# vreg.net
KiCad netlist of a schematic drawn in EAGLE
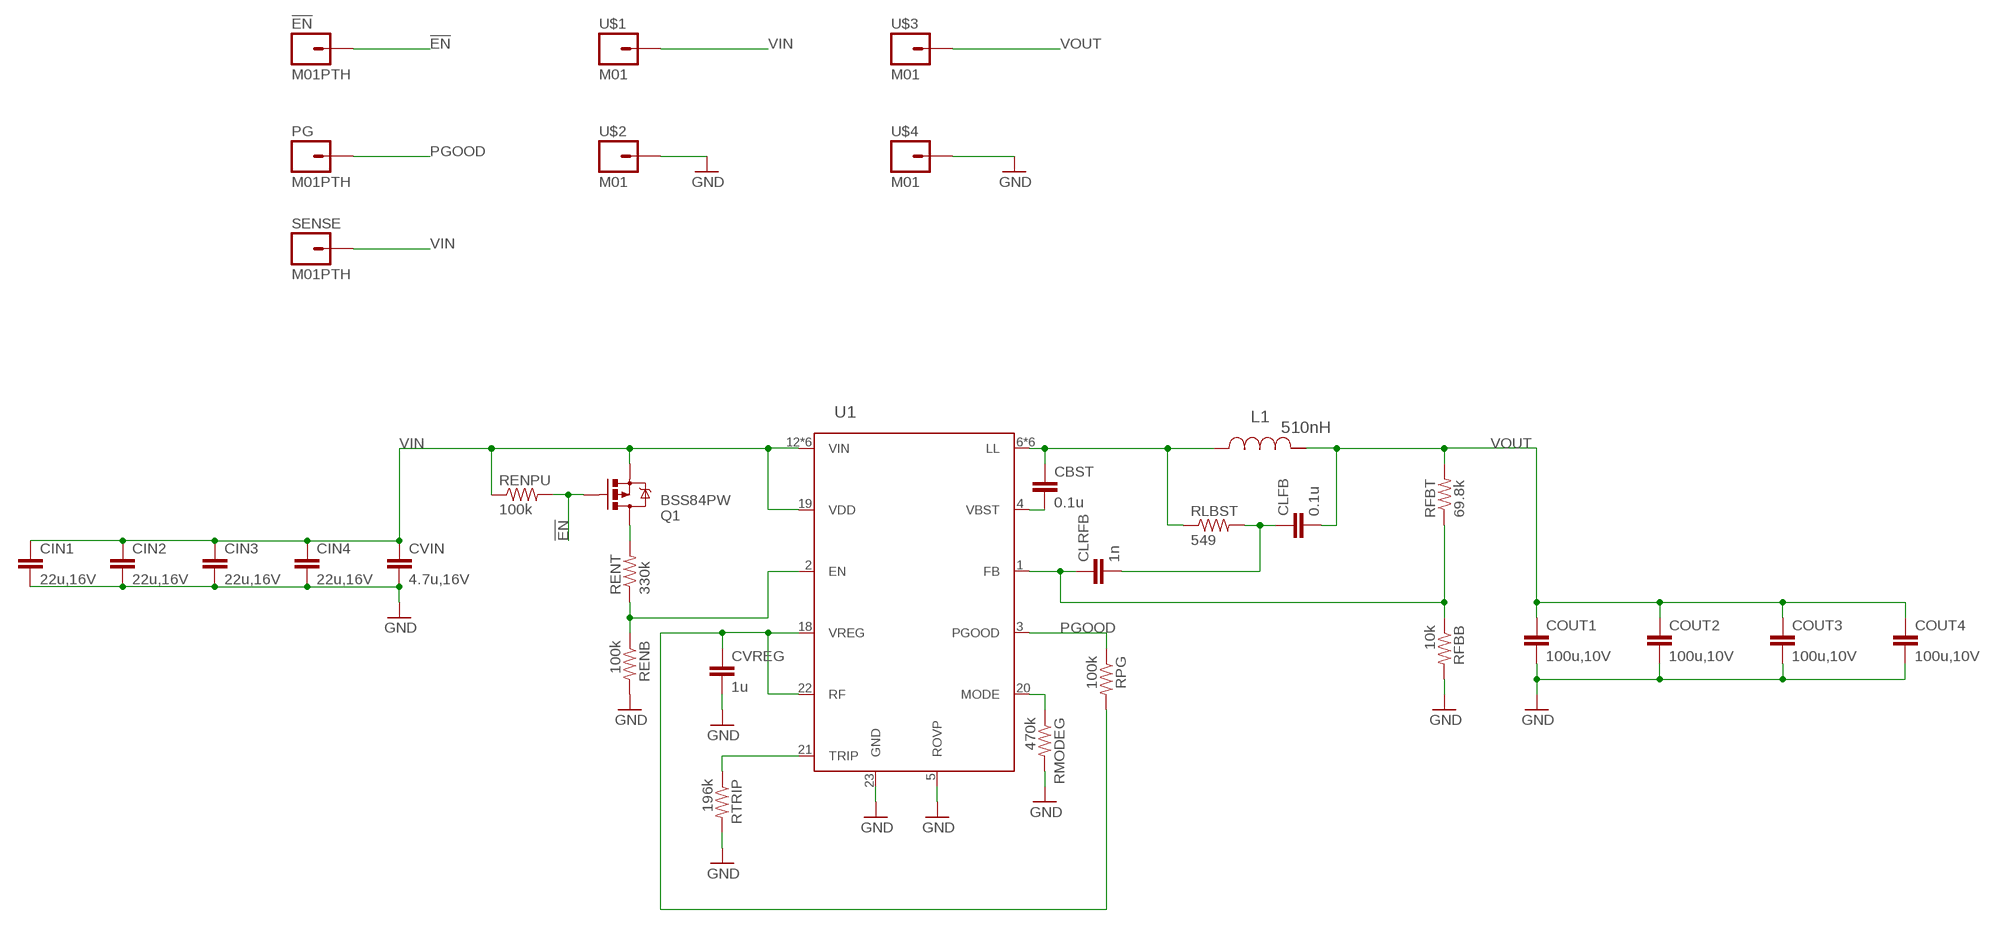
[diagram p0: schematic, sheet 1]

(export (version "E")
  (design (tool "Eeschema 10.0.6"))
  (components
    (comp (ref "!EN")
      (value "M01PTH")
      (footprint "eagle-import:1X01")
      (libsource (lib "eagle-import") (part "M01PTH"))
    )
    (comp (ref "CBST")
      (value "0.1u")
      (footprint "eagle-import:0603-CAP")
      (libsource (lib "eagle-import") (part "CAP0603-CAP"))
    )
    (comp (ref "CIN1")
      (value "22u,16V")
      (footprint "eagle-import:1210")
      (libsource (lib "eagle-import") (part "CAP1210"))
    )
    (comp (ref "CIN2")
      (value "22u,16V")
      (footprint "eagle-import:1210")
      (libsource (lib "eagle-import") (part "CAP1210"))
    )
    (comp (ref "CIN3")
      (value "22u,16V")
      (footprint "eagle-import:1210")
      (libsource (lib "eagle-import") (part "CAP1210"))
    )
    (comp (ref "CIN4")
      (value "22u,16V")
      (footprint "eagle-import:1210")
      (libsource (lib "eagle-import") (part "CAP1210"))
    )
    (comp (ref "CLFB")
      (value "0.1u")
      (footprint "eagle-import:0603-CAP")
      (libsource (lib "eagle-import") (part "CAP0603-CAP"))
    )
    (comp (ref "CLRFB")
      (value "1n")
      (footprint "eagle-import:0603-CAP")
      (libsource (lib "eagle-import") (part "CAP0603-CAP"))
    )
    (comp (ref "COUT1")
      (value "100u,10V")
      (footprint "eagle-import:1210")
      (libsource (lib "eagle-import") (part "CAP1210"))
    )
    (comp (ref "COUT2")
      (value "100u,10V")
      (footprint "eagle-import:1210")
      (libsource (lib "eagle-import") (part "CAP1210"))
    )
    (comp (ref "COUT3")
      (value "100u,10V")
      (footprint "eagle-import:1210")
      (libsource (lib "eagle-import") (part "CAP1210"))
    )
    (comp (ref "COUT4")
      (value "100u,10V")
      (footprint "eagle-import:1210")
      (libsource (lib "eagle-import") (part "CAP1210"))
    )
    (comp (ref "CVIN")
      (value "4.7u,16V")
      (footprint "eagle-import:1206")
      (libsource (lib "eagle-import") (part "CAP1206"))
    )
    (comp (ref "CVREG")
      (value "1u")
      (footprint "eagle-import:0603-CAP")
      (libsource (lib "eagle-import") (part "CAP0603-CAP"))
    )
    (comp (ref "L1")
      (value "510nH")
      (footprint "eagle-import:FP1107")
      (fields (field (name "MANUFACTURER_PART_NUMBER") "FP1107R1-R51-R"))
      (libsource (lib "eagle-import") (part "FP1107R1-R51-R"))
    )
    (comp (ref "PG")
      (value "M01PTH")
      (footprint "eagle-import:1X01")
      (libsource (lib "eagle-import") (part "M01PTH"))
    )
    (comp (ref "Q1")
      (value "BSS84PW")
      (footprint "eagle-import:SOT323")
      (libsource (lib "eagle-import") (part "BSS84PW"))
    )
    (comp (ref "RENB")
      (value "100k")
      (footprint "eagle-import:0603-RES")
      (libsource (lib "eagle-import") (part "RESISTOR0603"))
    )
    (comp (ref "RENPU")
      (value "100k")
      (footprint "eagle-import:0603-RES")
      (libsource (lib "eagle-import") (part "RESISTOR0603"))
    )
    (comp (ref "RENT")
      (value "330k")
      (footprint "eagle-import:0603-RES")
      (libsource (lib "eagle-import") (part "RESISTOR0603"))
    )
    (comp (ref "RFBB")
      (value "10k")
      (footprint "eagle-import:0603-RES")
      (libsource (lib "eagle-import") (part "RESISTOR0603"))
    )
    (comp (ref "RFBT")
      (value "69.8k")
      (footprint "eagle-import:0603-RES")
      (libsource (lib "eagle-import") (part "RESISTOR0603"))
    )
    (comp (ref "RLBST")
      (value "549")
      (footprint "eagle-import:0603-RES")
      (libsource (lib "eagle-import") (part "RESISTOR0603"))
    )
    (comp (ref "RMODEG")
      (value "470k")
      (footprint "eagle-import:0603-RES")
      (libsource (lib "eagle-import") (part "RESISTOR0603"))
    )
    (comp (ref "RPG")
      (value "100k")
      (footprint "eagle-import:0603-RES")
      (libsource (lib "eagle-import") (part "RESISTOR0603"))
    )
    (comp (ref "RTRIP")
      (value "196k")
      (footprint "eagle-import:0603-RES")
      (libsource (lib "eagle-import") (part "RESISTOR0603"))
    )
    (comp (ref "SENSE")
      (value "M01PTH")
      (footprint "eagle-import:1X01")
      (libsource (lib "eagle-import") (part "M01PTH"))
    )
    (comp (ref "U$1")
      (value "M01")
      (footprint "eagle-import:PIN_16AWG")
      (libsource (lib "eagle-import") (part "M01"))
    )
    (comp (ref "U$2")
      (value "M01")
      (footprint "eagle-import:PIN_16AWG")
      (libsource (lib "eagle-import") (part "M01"))
    )
    (comp (ref "U$3")
      (value "M01")
      (footprint "eagle-import:PIN_16AWG")
      (libsource (lib "eagle-import") (part "M01"))
    )
    (comp (ref "U$4")
      (value "M01")
      (footprint "eagle-import:PIN_16AWG")
      (libsource (lib "eagle-import") (part "M01"))
    )
    (comp (ref "U1")
      (value "TPS53319DQPR")
      (footprint "eagle-import:DQP0022A")
      (fields (field (name "MANUFACTURER_PART_NUMBER") "TPS53318DQPR"))
      (libsource (lib "eagle-import") (part "TPS53319DQPR"))
    )
  )
  (nets
    (net (code "1") (name "/PGOOD") (class "Default")
      (node (ref "PG") (pin "1") (pinfunction "1_1") (pintype "passive"))
      (node (ref "RPG") (pin "1") (pinfunction "1_1") (pintype "passive"))
      (node (ref "U1") (pin "3") (pinfunction "PGOOD_3") (pintype "passive"))
    )
    (net (code "2") (name "/VIN") (class "Default")
      (node (ref "CIN1") (pin "1") (pinfunction "1_1") (pintype "passive"))
      (node (ref "CIN2") (pin "1") (pinfunction "1_1") (pintype "passive"))
      (node (ref "CIN3") (pin "1") (pinfunction "1_1") (pintype "passive"))
      (node (ref "CIN4") (pin "1") (pinfunction "1_1") (pintype "passive"))
      (node (ref "CVIN") (pin "1") (pinfunction "1_1") (pintype "passive"))
      (node (ref "Q1") (pin "2") (pinfunction "S_2") (pintype "passive"))
      (node (ref "RENPU") (pin "1") (pinfunction "1_1") (pintype "passive"))
      (node (ref "SENSE") (pin "1") (pinfunction "1_1") (pintype "passive"))
      (node (ref "U$1") (pin "1") (pinfunction "1_1") (pintype "passive"))
      (node (ref "U1") (pin "12") (pinfunction "VIN_12") (pintype "passive"))
      (node (ref "U1") (pin "13") (pinfunction "VIN_13") (pintype "passive"))
      (node (ref "U1") (pin "14") (pinfunction "VIN_14") (pintype "passive"))
      (node (ref "U1") (pin "15") (pinfunction "VIN_15") (pintype "passive"))
      (node (ref "U1") (pin "16") (pinfunction "VIN_16") (pintype "passive"))
      (node (ref "U1") (pin "17") (pinfunction "VIN_17") (pintype "passive"))
      (node (ref "U1") (pin "19") (pinfunction "VDD_19") (pintype "passive"))
    )
    (net (code "3") (name "/VOUT") (class "Default")
      (node (ref "CLFB") (pin "2") (pinfunction "2_2") (pintype "passive"))
      (node (ref "COUT1") (pin "1") (pinfunction "1_1") (pintype "passive"))
      (node (ref "COUT2") (pin "1") (pinfunction "1_1") (pintype "passive"))
      (node (ref "COUT3") (pin "1") (pinfunction "1_1") (pintype "passive"))
      (node (ref "COUT4") (pin "1") (pinfunction "1_1") (pintype "passive"))
      (node (ref "L1") (pin "2") (pinfunction "2_2") (pintype "passive"))
      (node (ref "RFBT") (pin "2") (pinfunction "2_2") (pintype "passive"))
      (node (ref "U$3") (pin "1") (pinfunction "1_1") (pintype "passive"))
    )
    (net (code "4") (name "/~{EN}") (class "Default")
      (node (ref "!EN") (pin "1") (pinfunction "1_1") (pintype "passive"))
      (node (ref "Q1") (pin "1") (pinfunction "G_1") (pintype "passive"))
      (node (ref "RENPU") (pin "2") (pinfunction "2_2") (pintype "passive"))
    )
    (net (code "5") (name "GND") (class "Default")
      (node (ref "CIN1") (pin "2") (pinfunction "2_2") (pintype "passive"))
      (node (ref "CIN2") (pin "2") (pinfunction "2_2") (pintype "passive"))
      (node (ref "CIN3") (pin "2") (pinfunction "2_2") (pintype "passive"))
      (node (ref "CIN4") (pin "2") (pinfunction "2_2") (pintype "passive"))
      (node (ref "COUT1") (pin "2") (pinfunction "2_2") (pintype "passive"))
      (node (ref "COUT2") (pin "2") (pinfunction "2_2") (pintype "passive"))
      (node (ref "COUT3") (pin "2") (pinfunction "2_2") (pintype "passive"))
      (node (ref "COUT4") (pin "2") (pinfunction "2_2") (pintype "passive"))
      (node (ref "CVIN") (pin "2") (pinfunction "2_2") (pintype "passive"))
      (node (ref "CVREG") (pin "2") (pinfunction "2_2") (pintype "passive"))
      (node (ref "RENB") (pin "2") (pinfunction "2_2") (pintype "passive"))
      (node (ref "RFBB") (pin "2") (pinfunction "2_2") (pintype "passive"))
      (node (ref "RMODEG") (pin "2") (pinfunction "2_2") (pintype "passive"))
      (node (ref "RTRIP") (pin "2") (pinfunction "2_2") (pintype "passive"))
      (node (ref "U$2") (pin "1") (pinfunction "1_1") (pintype "passive"))
      (node (ref "U$4") (pin "1") (pinfunction "1_1") (pintype "passive"))
      (node (ref "U1") (pin "23") (pinfunction "GND_23") (pintype "passive"))
      (node (ref "U1") (pin "5") (pinfunction "ROVP_5") (pintype "passive"))
    )
    (net (code "6") (name "Net-(CBST-Pad1)") (class "Default")
      (node (ref "CBST") (pin "1") (pinfunction "1_1") (pintype "passive"))
      (node (ref "L1") (pin "1") (pinfunction "1_1") (pintype "passive"))
      (node (ref "RLBST") (pin "1") (pinfunction "1_1") (pintype "passive"))
      (node (ref "U1") (pin "10") (pinfunction "LL_10") (pintype "passive"))
      (node (ref "U1") (pin "11") (pinfunction "LL_11") (pintype "passive"))
      (node (ref "U1") (pin "6") (pinfunction "LL_6") (pintype "passive"))
      (node (ref "U1") (pin "7") (pinfunction "LL_7") (pintype "passive"))
      (node (ref "U1") (pin "8") (pinfunction "LL_8") (pintype "passive"))
      (node (ref "U1") (pin "9") (pinfunction "LL_9") (pintype "passive"))
    )
    (net (code "7") (name "Net-(CLFB-Pad1)") (class "Default")
      (node (ref "CLFB") (pin "1") (pinfunction "1_1") (pintype "passive"))
      (node (ref "CLRFB") (pin "2") (pinfunction "2_2") (pintype "passive"))
      (node (ref "RLBST") (pin "2") (pinfunction "2_2") (pintype "passive"))
    )
    (net (code "8") (name "Net-(Q1-D)") (class "Default")
      (node (ref "Q1") (pin "3") (pinfunction "D_3") (pintype "passive"))
      (node (ref "RENT") (pin "2") (pinfunction "2_2") (pintype "passive"))
    )
    (net (code "9") (name "Net-(U1-EN)") (class "Default")
      (node (ref "RENB") (pin "1") (pinfunction "1_1") (pintype "passive"))
      (node (ref "RENT") (pin "1") (pinfunction "1_1") (pintype "passive"))
      (node (ref "U1") (pin "2") (pinfunction "EN_2") (pintype "passive"))
    )
    (net (code "10") (name "Net-(U1-FB)") (class "Default")
      (node (ref "CLRFB") (pin "1") (pinfunction "1_1") (pintype "passive"))
      (node (ref "RFBB") (pin "1") (pinfunction "1_1") (pintype "passive"))
      (node (ref "RFBT") (pin "1") (pinfunction "1_1") (pintype "passive"))
      (node (ref "U1") (pin "1") (pinfunction "FB_1") (pintype "passive"))
    )
    (net (code "11") (name "Net-(U1-MODE)") (class "Default")
      (node (ref "RMODEG") (pin "1") (pinfunction "1_1") (pintype "passive"))
      (node (ref "U1") (pin "20") (pinfunction "MODE_20") (pintype "passive"))
    )
    (net (code "12") (name "Net-(U1-RF)") (class "Default")
      (node (ref "CVREG") (pin "1") (pinfunction "1_1") (pintype "passive"))
      (node (ref "RPG") (pin "2") (pinfunction "2_2") (pintype "passive"))
      (node (ref "U1") (pin "18") (pinfunction "VREG_18") (pintype "passive"))
      (node (ref "U1") (pin "22") (pinfunction "RF_22") (pintype "passive"))
    )
    (net (code "13") (name "Net-(U1-TRIP)") (class "Default")
      (node (ref "RTRIP") (pin "1") (pinfunction "1_1") (pintype "passive"))
      (node (ref "U1") (pin "21") (pinfunction "TRIP_21") (pintype "passive"))
    )
    (net (code "14") (name "Net-(U1-VBST)") (class "Default")
      (node (ref "CBST") (pin "2") (pinfunction "2_2") (pintype "passive"))
      (node (ref "U1") (pin "4") (pinfunction "VBST_4") (pintype "passive"))
    )
  )
)
